# IA-prop-raspberry.net
KiCad netlist of a schematic drawn in EAGLE
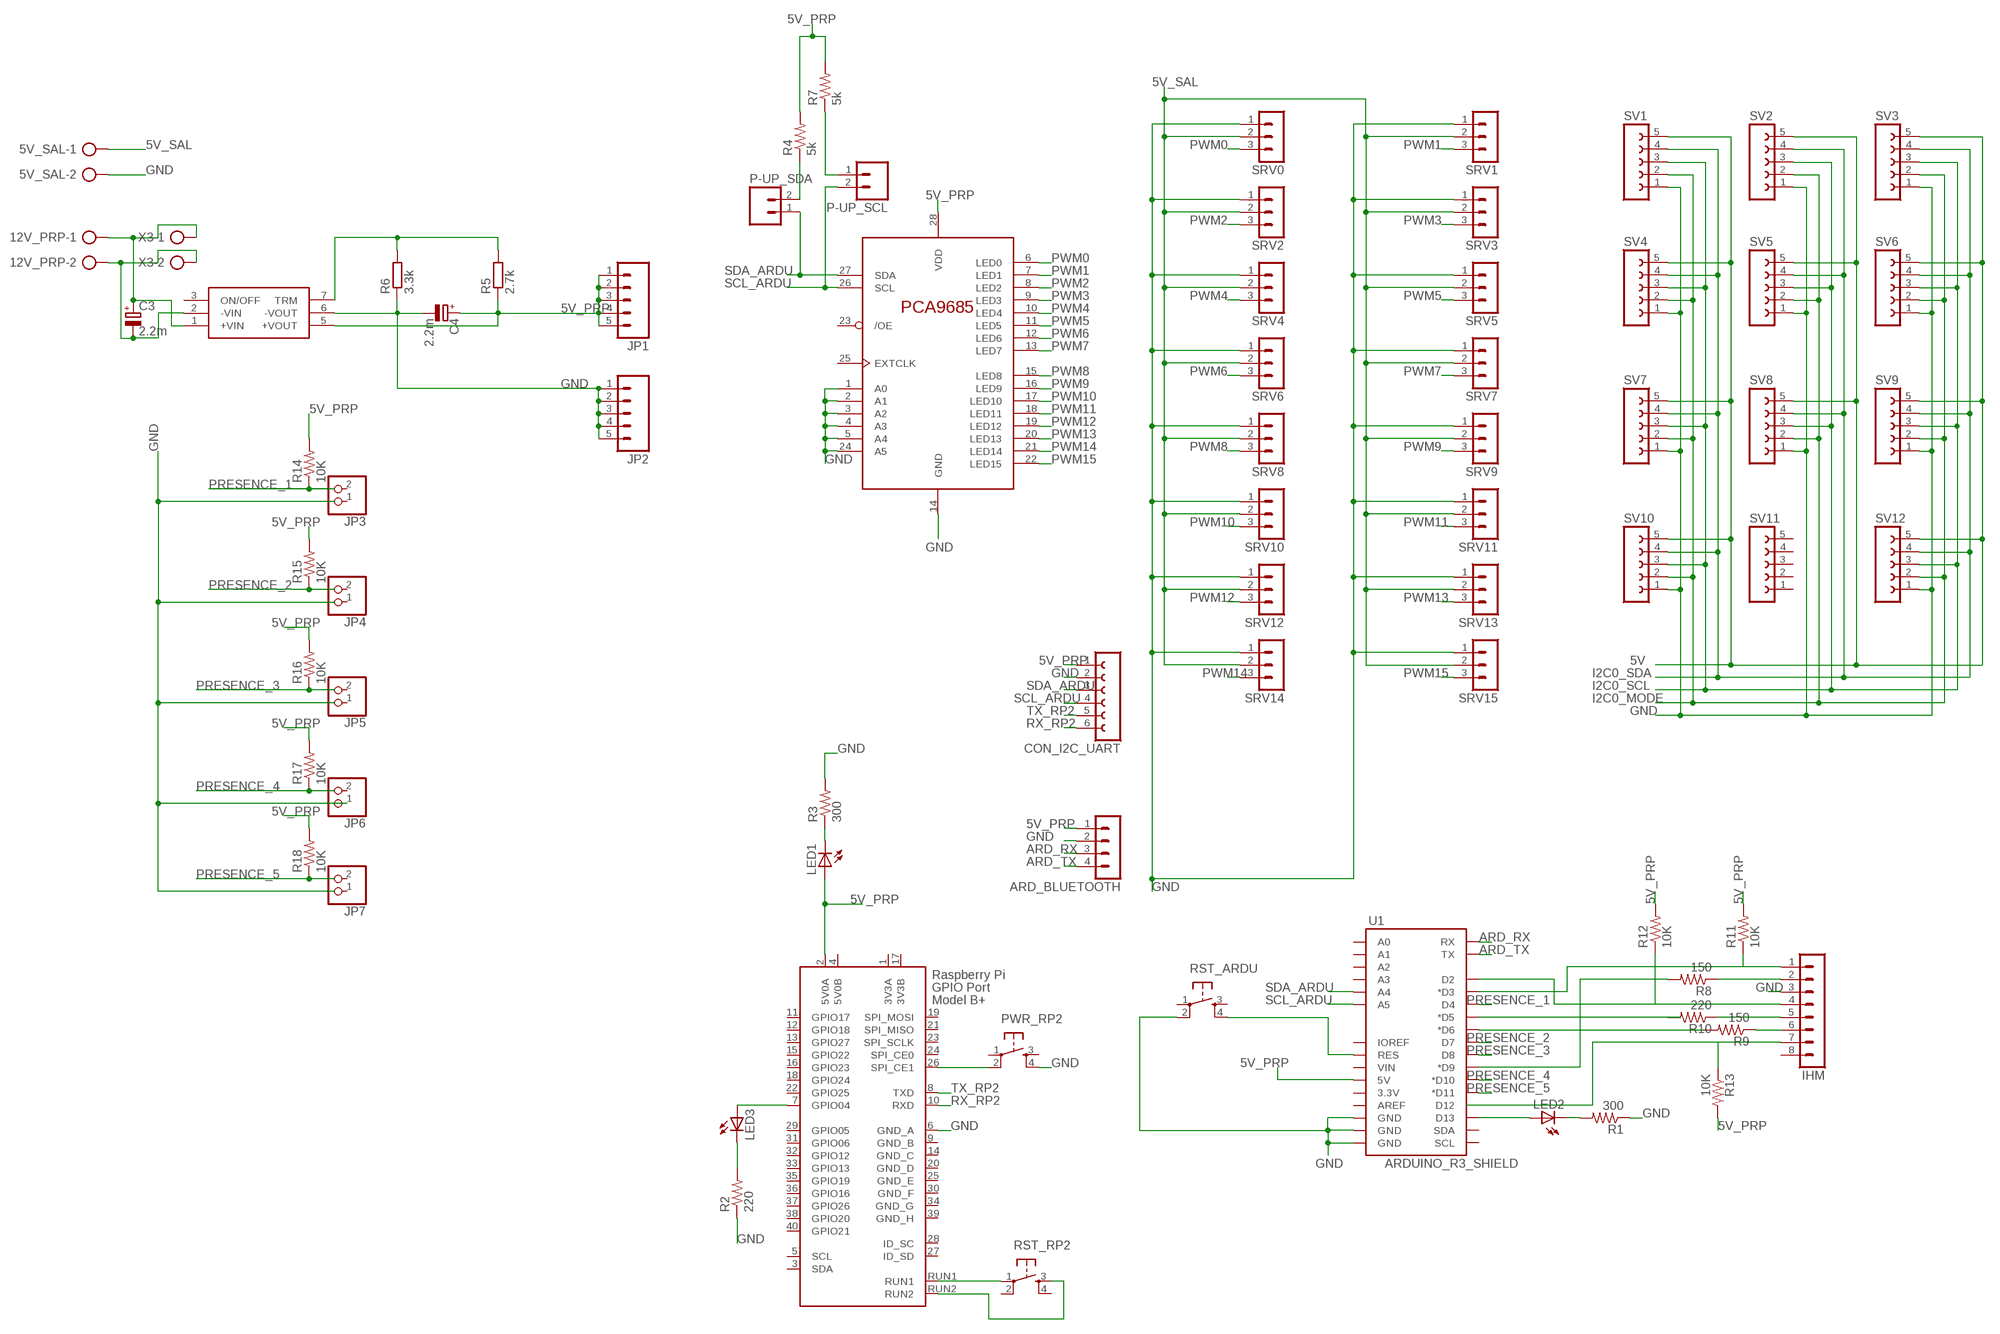
[diagram p0: schematic, sheet 1]

(export (version "E")
  (design (tool "Eeschema 10.0.6"))
  (components
    (comp (ref "5V_SAL")
      (value "AK300/2")
      (footprint "eagle-import:AK300_2")
      (fields (field (name "OC_FARNELL") "unknown") (field (name "OC_NEWARK") "unknown"))
      (libsource (lib "eagle-import") (part "AK300/2"))
    )
    (comp (ref "12V_PRP")
      (value "AK300/2")
      (footprint "eagle-import:AK300_2")
      (libsource (lib "eagle-import") (part "AK300/2"))
    )
    (comp (ref "ARD_BLUETOOTH")
      (value "MA04-1")
      (footprint "eagle-import:MA04-1")
      (libsource (lib "eagle-import") (part "MA04-1"))
    )
    (comp (ref "C3")
      (value "2.2m")
      (footprint "eagle-import:E5-13")
      (libsource (lib "eagle-import") (part "CPOL-EUE5-13"))
    )
    (comp (ref "C4")
      (value "2.2m")
      (footprint "eagle-import:E5-13")
      (libsource (lib "eagle-import") (part "CPOL-EUE5-13"))
    )
    (comp (ref "CON_I2C_UART")
      (value "FE06-1")
      (footprint "eagle-import:FE06")
      (fields (field (name "OC_FARNELL") "unknown") (field (name "OC_NEWARK") "unknown"))
      (libsource (lib "eagle-import") (part "FE06-1"))
    )
    (comp (ref "IHM")
      (value "MA08-1")
      (footprint "eagle-import:MA08-1")
      (libsource (lib "eagle-import") (part "MA08-1"))
    )
    (comp (ref "JP1")
      (value "M05PTH")
      (footprint "eagle-import:1X05")
      (libsource (lib "eagle-import") (part "M05PTH"))
    )
    (comp (ref "JP2")
      (value "M05PTH")
      (footprint "eagle-import:1X05")
      (libsource (lib "eagle-import") (part "M05PTH"))
    )
    (comp (ref "JP3")
      (value "PINHD-1X2")
      (footprint "eagle-import:1X02")
      (libsource (lib "eagle-import") (part "PINHD-1X2"))
    )
    (comp (ref "JP4")
      (value "PINHD-1X2")
      (footprint "eagle-import:1X02")
      (libsource (lib "eagle-import") (part "PINHD-1X2"))
    )
    (comp (ref "JP5")
      (value "PINHD-1X2")
      (footprint "eagle-import:1X02")
      (libsource (lib "eagle-import") (part "PINHD-1X2"))
    )
    (comp (ref "JP6")
      (value "PINHD-1X2")
      (footprint "eagle-import:1X02")
      (libsource (lib "eagle-import") (part "PINHD-1X2"))
    )
    (comp (ref "JP7")
      (value "PINHD-1X2")
      (footprint "eagle-import:1X02")
      (libsource (lib "eagle-import") (part "PINHD-1X2"))
    )
    (comp (ref "LED1")
      (value "LED3MM")
      (footprint "eagle-import:LED3MM")
      (libsource (lib "eagle-import") (part "LED3MM"))
    )
    (comp (ref "LED2")
      (value "LED3MM")
      (footprint "eagle-import:LED3MM")
      (libsource (lib "eagle-import") (part "LED3MM"))
    )
    (comp (ref "LED3")
      (value "LED3MM")
      (footprint "eagle-import:LED3MM")
      (libsource (lib "eagle-import") (part "LED3MM"))
    )
    (comp (ref "P-UP_SCL")
      (value "M02PTH")
      (footprint "eagle-import:1X02")
      (libsource (lib "eagle-import") (part "M02PTH"))
    )
    (comp (ref "P-UP_SDA")
      (value "M02PTH")
      (footprint "eagle-import:1X02")
      (libsource (lib "eagle-import") (part "M02PTH"))
    )
    (comp (ref "PWR_RP2")
      (value "TAC_SWITCHPTH")
      (footprint "eagle-import:TACTILE-PTH")
      (libsource (lib "eagle-import") (part "TAC_SWITCHPTH"))
    )
    (comp (ref "R1")
      (value "300")
      (footprint "eagle-import:AXIAL-0.3")
      (libsource (lib "eagle-import") (part "RESISTORAXIAL-0.3"))
    )
    (comp (ref "R2")
      (value "220")
      (footprint "eagle-import:AXIAL-0.3")
      (libsource (lib "eagle-import") (part "RESISTORAXIAL-0.3"))
    )
    (comp (ref "R3")
      (value "300")
      (footprint "eagle-import:AXIAL-0.3")
      (libsource (lib "eagle-import") (part "RESISTORAXIAL-0.3"))
    )
    (comp (ref "R4")
      (value "5k")
      (footprint "eagle-import:AXIAL-0.3")
      (libsource (lib "eagle-import") (part "RESISTORAXIAL-0.3"))
    )
    (comp (ref "R5")
      (value "2.7k")
      (footprint "eagle-import:0207_7")
      (libsource (lib "eagle-import") (part "R-EU_0207/7"))
    )
    (comp (ref "R6")
      (value "3.3k")
      (footprint "eagle-import:0207_7")
      (libsource (lib "eagle-import") (part "R-EU_0207/7"))
    )
    (comp (ref "R7")
      (value "5k")
      (footprint "eagle-import:AXIAL-0.3")
      (libsource (lib "eagle-import") (part "RESISTORAXIAL-0.3"))
    )
    (comp (ref "R8")
      (value "150")
      (footprint "eagle-import:AXIAL-0.3")
      (libsource (lib "eagle-import") (part "RESISTORAXIAL-0.3"))
    )
    (comp (ref "R9")
      (value "150")
      (footprint "eagle-import:AXIAL-0.3")
      (libsource (lib "eagle-import") (part "RESISTORAXIAL-0.3"))
    )
    (comp (ref "R10")
      (value "220")
      (footprint "eagle-import:AXIAL-0.3")
      (libsource (lib "eagle-import") (part "RESISTORAXIAL-0.3"))
    )
    (comp (ref "R11")
      (value "10K")
      (footprint "eagle-import:AXIAL-0.3")
      (libsource (lib "eagle-import") (part "RESISTORAXIAL-0.3"))
    )
    (comp (ref "R12")
      (value "10K")
      (footprint "eagle-import:AXIAL-0.3")
      (libsource (lib "eagle-import") (part "RESISTORAXIAL-0.3"))
    )
    (comp (ref "R13")
      (value "10K")
      (footprint "eagle-import:AXIAL-0.3")
      (libsource (lib "eagle-import") (part "RESISTORAXIAL-0.3"))
    )
    (comp (ref "R14")
      (value "10K")
      (footprint "eagle-import:AXIAL-0.3")
      (libsource (lib "eagle-import") (part "RESISTORAXIAL-0.3"))
    )
    (comp (ref "R15")
      (value "10K")
      (footprint "eagle-import:AXIAL-0.3")
      (libsource (lib "eagle-import") (part "RESISTORAXIAL-0.3"))
    )
    (comp (ref "R16")
      (value "10K")
      (footprint "eagle-import:AXIAL-0.3")
      (libsource (lib "eagle-import") (part "RESISTORAXIAL-0.3"))
    )
    (comp (ref "R17")
      (value "10K")
      (footprint "eagle-import:AXIAL-0.3")
      (libsource (lib "eagle-import") (part "RESISTORAXIAL-0.3"))
    )
    (comp (ref "R18")
      (value "10K")
      (footprint "eagle-import:AXIAL-0.3")
      (libsource (lib "eagle-import") (part "RESISTORAXIAL-0.3"))
    )
    (comp (ref "RP2")
      (value "RASPI_BOARD_B+#_FP")
      (footprint "eagle-import:RASPI_BOARD_B+_FULL_PAD")
      (libsource (lib "eagle-import") (part "RASPI_BOARD_B+#_FP"))
    )
    (comp (ref "RST_ARDU")
      (value "TAC_SWITCHPTH")
      (footprint "eagle-import:TACTILE-PTH")
      (libsource (lib "eagle-import") (part "TAC_SWITCHPTH"))
    )
    (comp (ref "RST_RP2")
      (value "TAC_SWITCHPTH")
      (footprint "eagle-import:TACTILE-PTH")
      (libsource (lib "eagle-import") (part "TAC_SWITCHPTH"))
    )
    (comp (ref "SRV0")
      (value "MA03-1")
      (footprint "eagle-import:MA03-1")
      (libsource (lib "eagle-import") (part "MA03-1"))
    )
    (comp (ref "SRV1")
      (value "MA03-1")
      (footprint "eagle-import:MA03-1")
      (libsource (lib "eagle-import") (part "MA03-1"))
    )
    (comp (ref "SRV2")
      (value "MA03-1")
      (footprint "eagle-import:MA03-1")
      (libsource (lib "eagle-import") (part "MA03-1"))
    )
    (comp (ref "SRV3")
      (value "MA03-1")
      (footprint "eagle-import:MA03-1")
      (libsource (lib "eagle-import") (part "MA03-1"))
    )
    (comp (ref "SRV4")
      (value "MA03-1")
      (footprint "eagle-import:MA03-1")
      (libsource (lib "eagle-import") (part "MA03-1"))
    )
    (comp (ref "SRV5")
      (value "MA03-1")
      (footprint "eagle-import:MA03-1")
      (libsource (lib "eagle-import") (part "MA03-1"))
    )
    (comp (ref "SRV6")
      (value "MA03-1")
      (footprint "eagle-import:MA03-1")
      (libsource (lib "eagle-import") (part "MA03-1"))
    )
    (comp (ref "SRV7")
      (value "MA03-1")
      (footprint "eagle-import:MA03-1")
      (libsource (lib "eagle-import") (part "MA03-1"))
    )
    (comp (ref "SRV8")
      (value "MA03-1")
      (footprint "eagle-import:MA03-1")
      (libsource (lib "eagle-import") (part "MA03-1"))
    )
    (comp (ref "SRV9")
      (value "MA03-1")
      (footprint "eagle-import:MA03-1")
      (libsource (lib "eagle-import") (part "MA03-1"))
    )
    (comp (ref "SRV10")
      (value "MA03-1")
      (footprint "eagle-import:MA03-1")
      (libsource (lib "eagle-import") (part "MA03-1"))
    )
    (comp (ref "SRV11")
      (value "MA03-1")
      (footprint "eagle-import:MA03-1")
      (libsource (lib "eagle-import") (part "MA03-1"))
    )
    (comp (ref "SRV12")
      (value "MA03-1")
      (footprint "eagle-import:MA03-1")
      (libsource (lib "eagle-import") (part "MA03-1"))
    )
    (comp (ref "SRV13")
      (value "MA03-1")
      (footprint "eagle-import:MA03-1")
      (libsource (lib "eagle-import") (part "MA03-1"))
    )
    (comp (ref "SRV14")
      (value "MA03-1")
      (footprint "eagle-import:MA03-1")
      (libsource (lib "eagle-import") (part "MA03-1"))
    )
    (comp (ref "SRV15")
      (value "MA03-1")
      (footprint "eagle-import:MA03-1")
      (libsource (lib "eagle-import") (part "MA03-1"))
    )
    (comp (ref "SV1")
      (value "FE05-1")
      (footprint "eagle-import:FE05-1")
      (libsource (lib "eagle-import") (part "FE05-1"))
    )
    (comp (ref "SV2")
      (value "FE05-1")
      (footprint "eagle-import:FE05-1")
      (fields (field (name "OC_FARNELL") "unknown") (field (name "OC_NEWARK") "unknown"))
      (libsource (lib "eagle-import") (part "FE05-1"))
    )
    (comp (ref "SV3")
      (value "FE05-1")
      (footprint "eagle-import:FE05-1")
      (fields (field (name "OC_FARNELL") "unknown") (field (name "OC_NEWARK") "unknown"))
      (libsource (lib "eagle-import") (part "FE05-1"))
    )
    (comp (ref "SV4")
      (value "FE05-1")
      (footprint "eagle-import:FE05-1")
      (libsource (lib "eagle-import") (part "FE05-1"))
    )
    (comp (ref "SV5")
      (value "FE05-1")
      (footprint "eagle-import:FE05-1")
      (fields (field (name "OC_FARNELL") "unknown") (field (name "OC_NEWARK") "unknown"))
      (libsource (lib "eagle-import") (part "FE05-1"))
    )
    (comp (ref "SV6")
      (value "FE05-1")
      (footprint "eagle-import:FE05-1")
      (fields (field (name "OC_FARNELL") "unknown") (field (name "OC_NEWARK") "unknown"))
      (libsource (lib "eagle-import") (part "FE05-1"))
    )
    (comp (ref "SV7")
      (value "FE05-1")
      (footprint "eagle-import:FE05-1")
      (libsource (lib "eagle-import") (part "FE05-1"))
    )
    (comp (ref "SV8")
      (value "FE05-1")
      (footprint "eagle-import:FE05-1")
      (fields (field (name "OC_FARNELL") "unknown") (field (name "OC_NEWARK") "unknown"))
      (libsource (lib "eagle-import") (part "FE05-1"))
    )
    (comp (ref "SV9")
      (value "FE05-1")
      (footprint "eagle-import:FE05-1")
      (fields (field (name "OC_FARNELL") "unknown") (field (name "OC_NEWARK") "unknown"))
      (libsource (lib "eagle-import") (part "FE05-1"))
    )
    (comp (ref "SV10")
      (value "FE05-1")
      (footprint "eagle-import:FE05-1")
      (libsource (lib "eagle-import") (part "FE05-1"))
    )
    (comp (ref "SV11")
      (value "FE05-1")
      (footprint "eagle-import:FE05-1")
      (fields (field (name "OC_FARNELL") "unknown") (field (name "OC_NEWARK") "unknown"))
      (libsource (lib "eagle-import") (part "FE05-1"))
    )
    (comp (ref "SV12")
      (value "FE05-1")
      (footprint "eagle-import:FE05-1")
      (fields (field (name "OC_FARNELL") "unknown") (field (name "OC_NEWARK") "unknown"))
      (libsource (lib "eagle-import") (part "FE05-1"))
    )
    (comp (ref "U$1")
      (value "PCA9685PW")
      (footprint "eagle-import:TSSOP28")
      (libsource (lib "eagle-import") (part "PCA9685PW"))
    )
    (comp (ref "U$2")
      (value "TEN25-1211TEN25-1211")
      (footprint "eagle-import:TEN25")
      (libsource (lib "eagle-import") (part "TEN25-1211TEN25-1211"))
    )
    (comp (ref "U1")
      (value "ARDUINO_R3_SHIELD")
      (footprint "eagle-import:UNO_R3_SHIELD")
      (libsource (lib "eagle-import") (part "ARDUINO_R3_SHIELD"))
    )
    (comp (ref "X3")
      (value "AK300/2")
      (footprint "eagle-import:AK300_2")
      (libsource (lib "eagle-import") (part "AK300/2"))
    )
  )
  (nets
    (net (code "1") (name "/3V3A") (class "Default")
      (node (ref "RP2") (pin "1") (pinfunction "3V3A_1") (pintype "power_in"))
    )
    (net (code "2") (name "/3V3B") (class "Default")
      (node (ref "RP2") (pin "17") (pinfunction "3V3B_17") (pintype "power_in"))
    )
    (net (code "3") (name "/5V") (class "Default")
      (node (ref "SV1") (pin "5") (pinfunction "5_5") (pintype "passive"))
      (node (ref "SV10") (pin "5") (pinfunction "5_5") (pintype "passive"))
      (node (ref "SV12") (pin "5") (pinfunction "5_5") (pintype "passive"))
      (node (ref "SV2") (pin "5") (pinfunction "5_5") (pintype "passive"))
      (node (ref "SV3") (pin "5") (pinfunction "5_5") (pintype "passive"))
      (node (ref "SV4") (pin "5") (pinfunction "5_5") (pintype "passive"))
      (node (ref "SV5") (pin "5") (pinfunction "5_5") (pintype "passive"))
      (node (ref "SV6") (pin "5") (pinfunction "5_5") (pintype "passive"))
      (node (ref "SV7") (pin "5") (pinfunction "5_5") (pintype "passive"))
      (node (ref "SV8") (pin "5") (pinfunction "5_5") (pintype "passive"))
      (node (ref "SV9") (pin "5") (pinfunction "5_5") (pintype "passive"))
    )
    (net (code "4") (name "/5V0B") (class "Default")
      (node (ref "RP2") (pin "4") (pinfunction "5V0B_4") (pintype "power_in"))
    )
    (net (code "5") (name "/5V_PRP") (class "Default")
      (node (ref "ARD_BLUETOOTH") (pin "1") (pinfunction "1_1") (pintype "passive"))
      (node (ref "C4") (pin "+") (pinfunction "+_+") (pintype "passive"))
      (node (ref "CON_I2C_UART") (pin "1") (pinfunction "1_1") (pintype "passive"))
      (node (ref "JP1") (pin "1") (pinfunction "1_1") (pintype "passive"))
      (node (ref "JP1") (pin "2") (pinfunction "2_2") (pintype "passive"))
      (node (ref "JP1") (pin "3") (pinfunction "3_3") (pintype "passive"))
      (node (ref "JP1") (pin "4") (pinfunction "4_4") (pintype "passive"))
      (node (ref "JP1") (pin "5") (pinfunction "5_5") (pintype "passive"))
      (node (ref "LED1") (pin "A") (pinfunction "A_A") (pintype "passive"))
      (node (ref "R11") (pin "P$2") (pinfunction "2_P$2") (pintype "passive"))
      (node (ref "R12") (pin "P$2") (pinfunction "2_P$2") (pintype "passive"))
      (node (ref "R13") (pin "P$2") (pinfunction "2_P$2") (pintype "passive"))
      (node (ref "R14") (pin "P$2") (pinfunction "2_P$2") (pintype "passive"))
      (node (ref "R15") (pin "P$2") (pinfunction "2_P$2") (pintype "passive"))
      (node (ref "R16") (pin "P$2") (pinfunction "2_P$2") (pintype "passive"))
      (node (ref "R17") (pin "P$2") (pinfunction "2_P$2") (pintype "passive"))
      (node (ref "R18") (pin "P$2") (pinfunction "2_P$2") (pintype "passive"))
      (node (ref "R4") (pin "P$2") (pinfunction "2_P$2") (pintype "passive"))
      (node (ref "R5") (pin "1") (pinfunction "1_1") (pintype "passive"))
      (node (ref "R7") (pin "P$2") (pinfunction "2_P$2") (pintype "passive"))
      (node (ref "RP2") (pin "2") (pinfunction "5V0A_2") (pintype "power_in"))
      (node (ref "U$1") (pin "28") (pinfunction "VDD_28") (pintype "power_in"))
      (node (ref "U$2") (pin "5") (pinfunction "+VOUT_5") (pintype "bidirectional"))
      (node (ref "U1") (pin "5V") (pinfunction "5V_5V") (pintype "bidirectional"))
    )
    (net (code "6") (name "/5V_SAL") (class "Default")
      (node (ref "5V_SAL") (pin "1") (pinfunction "KL_1") (pintype "passive"))
      (node (ref "SRV0") (pin "2") (pinfunction "2_2") (pintype "passive"))
      (node (ref "SRV1") (pin "2") (pinfunction "2_2") (pintype "passive"))
      (node (ref "SRV10") (pin "2") (pinfunction "2_2") (pintype "passive"))
      (node (ref "SRV11") (pin "2") (pinfunction "2_2") (pintype "passive"))
      (node (ref "SRV12") (pin "2") (pinfunction "2_2") (pintype "passive"))
      (node (ref "SRV13") (pin "2") (pinfunction "2_2") (pintype "passive"))
      (node (ref "SRV14") (pin "2") (pinfunction "2_2") (pintype "passive"))
      (node (ref "SRV15") (pin "2") (pinfunction "2_2") (pintype "passive"))
      (node (ref "SRV2") (pin "2") (pinfunction "2_2") (pintype "passive"))
      (node (ref "SRV3") (pin "2") (pinfunction "2_2") (pintype "passive"))
      (node (ref "SRV4") (pin "2") (pinfunction "2_2") (pintype "passive"))
      (node (ref "SRV5") (pin "2") (pinfunction "2_2") (pintype "passive"))
      (node (ref "SRV6") (pin "2") (pinfunction "2_2") (pintype "passive"))
      (node (ref "SRV7") (pin "2") (pinfunction "2_2") (pintype "passive"))
      (node (ref "SRV8") (pin "2") (pinfunction "2_2") (pintype "passive"))
      (node (ref "SRV9") (pin "2") (pinfunction "2_2") (pintype "passive"))
    )
    (net (code "7") (name "/ARD_RX") (class "Default")
      (node (ref "ARD_BLUETOOTH") (pin "3") (pinfunction "3_3") (pintype "passive"))
      (node (ref "U1") (pin "RX") (pinfunction "RX_RX") (pintype "bidirectional"))
    )
    (net (code "8") (name "/ARD_TX") (class "Default")
      (node (ref "ARD_BLUETOOTH") (pin "4") (pinfunction "4_4") (pintype "passive"))
      (node (ref "U1") (pin "TX") (pinfunction "TX_TX") (pintype "bidirectional"))
    )
    (net (code "9") (name "/GND") (class "Default")
      (node (ref "5V_SAL") (pin "2") (pinfunction "KL_2") (pintype "passive"))
      (node (ref "ARD_BLUETOOTH") (pin "2") (pinfunction "2_2") (pintype "passive"))
      (node (ref "C4") (pin "-") (pinfunction "-_-") (pintype "passive"))
      (node (ref "CON_I2C_UART") (pin "2") (pinfunction "2_2") (pintype "passive"))
      (node (ref "IHM") (pin "3") (pinfunction "3_3") (pintype "passive"))
      (node (ref "JP2") (pin "1") (pinfunction "1_1") (pintype "passive"))
      (node (ref "JP2") (pin "2") (pinfunction "2_2") (pintype "passive"))
      (node (ref "JP2") (pin "3") (pinfunction "3_3") (pintype "passive"))
      (node (ref "JP2") (pin "4") (pinfunction "4_4") (pintype "passive"))
      (node (ref "JP2") (pin "5") (pinfunction "5_5") (pintype "passive"))
      (node (ref "JP6") (pin "1") (pinfunction "1_1") (pintype "passive"))
      (node (ref "PWR_RP2") (pin "4") (pinfunction "4_4") (pintype "passive"))
      (node (ref "R1") (pin "P$1") (pinfunction "1_P$1") (pintype "passive"))
      (node (ref "R2") (pin "P$1") (pinfunction "1_P$1") (pintype "passive"))
      (node (ref "R3") (pin "P$2") (pinfunction "2_P$2") (pintype "passive"))
      (node (ref "R6") (pin "1") (pinfunction "1_1") (pintype "passive"))
      (node (ref "RP2") (pin "6") (pinfunction "GND_A_6") (pintype "power_in"))
      (node (ref "RST_ARDU") (pin "2") (pinfunction "2_2") (pintype "passive"))
      (node (ref "SRV0") (pin "1") (pinfunction "1_1") (pintype "passive"))
      (node (ref "SRV1") (pin "1") (pinfunction "1_1") (pintype "passive"))
      (node (ref "SRV10") (pin "1") (pinfunction "1_1") (pintype "passive"))
      (node (ref "SRV11") (pin "1") (pinfunction "1_1") (pintype "passive"))
      (node (ref "SRV12") (pin "1") (pinfunction "1_1") (pintype "passive"))
      (node (ref "SRV13") (pin "1") (pinfunction "1_1") (pintype "passive"))
      (node (ref "SRV14") (pin "1") (pinfunction "1_1") (pintype "passive"))
      (node (ref "SRV15") (pin "1") (pinfunction "1_1") (pintype "passive"))
      (node (ref "SRV2") (pin "1") (pinfunction "1_1") (pintype "passive"))
      (node (ref "SRV3") (pin "1") (pinfunction "1_1") (pintype "passive"))
      (node (ref "SRV4") (pin "1") (pinfunction "1_1") (pintype "passive"))
      (node (ref "SRV5") (pin "1") (pinfunction "1_1") (pintype "passive"))
      (node (ref "SRV6") (pin "1") (pinfunction "1_1") (pintype "passive"))
      (node (ref "SRV7") (pin "1") (pinfunction "1_1") (pintype "passive"))
      (node (ref "SRV8") (pin "1") (pinfunction "1_1") (pintype "passive"))
      (node (ref "SRV9") (pin "1") (pinfunction "1_1") (pintype "passive"))
      (node (ref "SV1") (pin "1") (pinfunction "1_1") (pintype "passive"))
      (node (ref "SV10") (pin "1") (pinfunction "1_1") (pintype "passive"))
      (node (ref "SV12") (pin "1") (pinfunction "1_1") (pintype "passive"))
      (node (ref "SV2") (pin "1") (pinfunction "1_1") (pintype "passive"))
      (node (ref "SV3") (pin "1") (pinfunction "1_1") (pintype "passive"))
      (node (ref "SV4") (pin "1") (pinfunction "1_1") (pintype "passive"))
      (node (ref "SV5") (pin "1") (pinfunction "1_1") (pintype "passive"))
      (node (ref "SV6") (pin "1") (pinfunction "1_1") (pintype "passive"))
      (node (ref "SV7") (pin "1") (pinfunction "1_1") (pintype "passive"))
      (node (ref "SV8") (pin "1") (pinfunction "1_1") (pintype "passive"))
      (node (ref "SV9") (pin "1") (pinfunction "1_1") (pintype "passive"))
      (node (ref "U$1") (pin "1") (pinfunction "A0_1") (pintype "bidirectional"))
      (node (ref "U$1") (pin "14") (pinfunction "GND_14") (pintype "power_in"))
      (node (ref "U$1") (pin "2") (pinfunction "A1_2") (pintype "bidirectional"))
      (node (ref "U$1") (pin "24") (pinfunction "A5_24") (pintype "bidirectional"))
      (node (ref "U$1") (pin "3") (pinfunction "A2_3") (pintype "bidirectional"))
      (node (ref "U$1") (pin "4") (pinfunction "A3_4") (pintype "bidirectional"))
      (node (ref "U$1") (pin "5") (pinfunction "A4_5") (pintype "bidirectional"))
      (node (ref "U$2") (pin "6") (pinfunction "-VOUT_6") (pintype "bidirectional"))
      (node (ref "U1") (pin "GND@0") (pinfunction "GND_GND@0") (pintype "bidirectional"))
      (node (ref "U1") (pin "GND@1") (pinfunction "GND_GND@1") (pintype "bidirectional"))
      (node (ref "U1") (pin "GND@2") (pinfunction "GND_GND@2") (pintype "bidirectional"))
    )
    (net (code "10") (name "/GND_B") (class "Default")
      (node (ref "RP2") (pin "9") (pinfunction "GND_B_9") (pintype "power_in"))
    )
    (net (code "11") (name "/GND_C") (class "Default")
      (node (ref "RP2") (pin "14") (pinfunction "GND_C_14") (pintype "power_in"))
    )
    (net (code "12") (name "/GND_D") (class "Default")
      (node (ref "RP2") (pin "20") (pinfunction "GND_D_20") (pintype "power_in"))
    )
    (net (code "13") (name "/GND_E") (class "Default")
      (node (ref "RP2") (pin "25") (pinfunction "GND_E_25") (pintype "power_in"))
    )
    (net (code "14") (name "/GND_F") (class "Default")
      (node (ref "RP2") (pin "30") (pinfunction "GND_F_30") (pintype "power_in"))
    )
    (net (code "15") (name "/GND_G") (class "Default")
      (node (ref "RP2") (pin "34") (pinfunction "GND_G_34") (pintype "power_in"))
    )
    (net (code "16") (name "/GND_H") (class "Default")
      (node (ref "RP2") (pin "39") (pinfunction "GND_H_39") (pintype "power_in"))
    )
    (net (code "17") (name "/I2C0_MODE") (class "Default")
      (node (ref "SV1") (pin "2") (pinfunction "2_2") (pintype "passive"))
      (node (ref "SV10") (pin "2") (pinfunction "2_2") (pintype "passive"))
      (node (ref "SV12") (pin "2") (pinfunction "2_2") (pintype "passive"))
      (node (ref "SV2") (pin "2") (pinfunction "2_2") (pintype "passive"))
      (node (ref "SV3") (pin "2") (pinfunction "2_2") (pintype "passive"))
      (node (ref "SV4") (pin "2") (pinfunction "2_2") (pintype "passive"))
      (node (ref "SV5") (pin "2") (pinfunction "2_2") (pintype "passive"))
      (node (ref "SV6") (pin "2") (pinfunction "2_2") (pintype "passive"))
      (node (ref "SV7") (pin "2") (pinfunction "2_2") (pintype "passive"))
      (node (ref "SV8") (pin "2") (pinfunction "2_2") (pintype "passive"))
      (node (ref "SV9") (pin "2") (pinfunction "2_2") (pintype "passive"))
    )
    (net (code "18") (name "/I2C0_SCL") (class "Default")
      (node (ref "SV1") (pin "3") (pinfunction "3_3") (pintype "passive"))
      (node (ref "SV10") (pin "3") (pinfunction "3_3") (pintype "passive"))
      (node (ref "SV12") (pin "3") (pinfunction "3_3") (pintype "passive"))
      (node (ref "SV2") (pin "3") (pinfunction "3_3") (pintype "passive"))
      (node (ref "SV3") (pin "3") (pinfunction "3_3") (pintype "passive"))
      (node (ref "SV4") (pin "3") (pinfunction "3_3") (pintype "passive"))
      (node (ref "SV5") (pin "3") (pinfunction "3_3") (pintype "passive"))
      (node (ref "SV6") (pin "3") (pinfunction "3_3") (pintype "passive"))
      (node (ref "SV7") (pin "3") (pinfunction "3_3") (pintype "passive"))
      (node (ref "SV8") (pin "3") (pinfunction "3_3") (pintype "passive"))
      (node (ref "SV9") (pin "3") (pinfunction "3_3") (pintype "passive"))
    )
    (net (code "19") (name "/I2C0_SDA") (class "Default")
      (node (ref "SV1") (pin "4") (pinfunction "4_4") (pintype "passive"))
      (node (ref "SV10") (pin "4") (pinfunction "4_4") (pintype "passive"))
      (node (ref "SV12") (pin "4") (pinfunction "4_4") (pintype "passive"))
      (node (ref "SV2") (pin "4") (pinfunction "4_4") (pintype "passive"))
      (node (ref "SV3") (pin "4") (pinfunction "4_4") (pintype "passive"))
      (node (ref "SV4") (pin "4") (pinfunction "4_4") (pintype "passive"))
      (node (ref "SV5") (pin "4") (pinfunction "4_4") (pintype "passive"))
      (node (ref "SV6") (pin "4") (pinfunction "4_4") (pintype "passive"))
      (node (ref "SV7") (pin "4") (pinfunction "4_4") (pintype "passive"))
      (node (ref "SV8") (pin "4") (pinfunction "4_4") (pintype "passive"))
      (node (ref "SV9") (pin "4") (pinfunction "4_4") (pintype "passive"))
    )
    (net (code "20") (name "/PRESENCE_1") (class "Default")
      (node (ref "R14") (pin "P$1") (pinfunction "1_P$1") (pintype "passive"))
      (node (ref "U1") (pin "D4") (pinfunction "D4_D4") (pintype "bidirectional"))
    )
    (net (code "21") (name "/PRESENCE_2") (class "Default")
      (node (ref "R15") (pin "P$1") (pinfunction "1_P$1") (pintype "passive"))
      (node (ref "U1") (pin "D7") (pinfunction "D7_D7") (pintype "bidirectional"))
    )
    (net (code "22") (name "/PRESENCE_3") (class "Default")
      (node (ref "R16") (pin "P$1") (pinfunction "1_P$1") (pintype "passive"))
      (node (ref "U1") (pin "D8") (pinfunction "D8_D8") (pintype "bidirectional"))
    )
    (net (code "23") (name "/PRESENCE_4") (class "Default")
      (node (ref "R17") (pin "P$1") (pinfunction "1_P$1") (pintype "passive"))
      (node (ref "U1") (pin "D10") (pinfunction "*D10_D10") (pintype "bidirectional"))
    )
    (net (code "24") (name "/PRESENCE_5") (class "Default")
      (node (ref "R18") (pin "P$1") (pinfunction "1_P$1") (pintype "passive"))
      (node (ref "U1") (pin "D11") (pinfunction "*D11_D11") (pintype "bidirectional"))
    )
    (net (code "25") (name "/PWM0") (class "Default")
      (node (ref "SRV0") (pin "3") (pinfunction "3_3") (pintype "passive"))
      (node (ref "U$1") (pin "6") (pinfunction "LED0_6") (pintype "bidirectional"))
    )
    (net (code "26") (name "/PWM1") (class "Default")
      (node (ref "SRV1") (pin "3") (pinfunction "3_3") (pintype "passive"))
      (node (ref "U$1") (pin "7") (pinfunction "LED1_7") (pintype "bidirectional"))
    )
    (net (code "27") (name "/PWM2") (class "Default")
      (node (ref "SRV2") (pin "3") (pinfunction "3_3") (pintype "passive"))
      (node (ref "U$1") (pin "8") (pinfunction "LED2_8") (pintype "bidirectional"))
    )
    (net (code "28") (name "/PWM3") (class "Default")
      (node (ref "SRV3") (pin "3") (pinfunction "3_3") (pintype "passive"))
      (node (ref "U$1") (pin "9") (pinfunction "LED3_9") (pintype "bidirectional"))
    )
    (net (code "29") (name "/PWM4") (class "Default")
      (node (ref "SRV4") (pin "3") (pinfunction "3_3") (pintype "passive"))
      (node (ref "U$1") (pin "10") (pinfunction "LED4_10") (pintype "bidirectional"))
    )
    (net (code "30") (name "/PWM5") (class "Default")
      (node (ref "SRV5") (pin "3") (pinfunction "3_3") (pintype "passive"))
      (node (ref "U$1") (pin "11") (pinfunction "LED5_11") (pintype "bidirectional"))
    )
    (net (code "31") (name "/PWM6") (class "Default")
      (node (ref "SRV6") (pin "3") (pinfunction "3_3") (pintype "passive"))
      (node (ref "U$1") (pin "12") (pinfunction "LED6_12") (pintype "bidirectional"))
    )
    (net (code "32") (name "/PWM7") (class "Default")
      (node (ref "SRV7") (pin "3") (pinfunction "3_3") (pintype "passive"))
      (node (ref "U$1") (pin "13") (pinfunction "LED7_13") (pintype "bidirectional"))
    )
    (net (code "33") (name "/PWM8") (class "Default")
      (node (ref "SRV8") (pin "3") (pinfunction "3_3") (pintype "passive"))
      (node (ref "U$1") (pin "15") (pinfunction "LED8_15") (pintype "bidirectional"))
    )
    (net (code "34") (name "/PWM9") (class "Default")
      (node (ref "SRV9") (pin "3") (pinfunction "3_3") (pintype "passive"))
      (node (ref "U$1") (pin "16") (pinfunction "LED9_16") (pintype "bidirectional"))
    )
    (net (code "35") (name "/PWM10") (class "Default")
      (node (ref "SRV10") (pin "3") (pinfunction "3_3") (pintype "passive"))
      (node (ref "U$1") (pin "17") (pinfunction "LED10_17") (pintype "bidirectional"))
    )
    (net (code "36") (name "/PWM11") (class "Default")
      (node (ref "SRV11") (pin "3") (pinfunction "3_3") (pintype "passive"))
      (node (ref "U$1") (pin "18") (pinfunction "LED11_18") (pintype "bidirectional"))
    )
    (net (code "37") (name "/PWM12") (class "Default")
      (node (ref "SRV12") (pin "3") (pinfunction "3_3") (pintype "passive"))
      (node (ref "U$1") (pin "19") (pinfunction "LED12_19") (pintype "bidirectional"))
    )
    (net (code "38") (name "/PWM13") (class "Default")
      (node (ref "SRV13") (pin "3") (pinfunction "3_3") (pintype "passive"))
      (node (ref "U$1") (pin "20") (pinfunction "LED13_20") (pintype "bidirectional"))
    )
    (net (code "39") (name "/PWM14") (class "Default")
      (node (ref "SRV14") (pin "3") (pinfunction "3_3") (pintype "passive"))
      (node (ref "U$1") (pin "21") (pinfunction "LED14_21") (pintype "bidirectional"))
    )
    (net (code "40") (name "/PWM15") (class "Default")
      (node (ref "SRV15") (pin "3") (pinfunction "3_3") (pintype "passive"))
      (node (ref "U$1") (pin "22") (pinfunction "LED15_22") (pintype "bidirectional"))
    )
    (net (code "41") (name "/RX_RP2") (class "Default")
      (node (ref "CON_I2C_UART") (pin "6") (pinfunction "6_6") (pintype "passive"))
      (node (ref "RP2") (pin "10") (pinfunction "RXD_10") (pintype "bidirectional"))
    )
    (net (code "42") (name "/SCL_ARDU") (class "Default")
      (node (ref "CON_I2C_UART") (pin "4") (pinfunction "4_4") (pintype "passive"))
      (node (ref "P-UP_SCL") (pin "2") (pinfunction "2_2") (pintype "passive"))
      (node (ref "U$1") (pin "26") (pinfunction "SCL_26") (pintype "bidirectional"))
      (node (ref "U1") (pin "A5") (pinfunction "A5_A5") (pintype "bidirectional"))
    )
    (net (code "43") (name "/SDA_ARDU") (class "Default")
      (node (ref "CON_I2C_UART") (pin "3") (pinfunction "3_3") (pintype "passive"))
      (node (ref "P-UP_SDA") (pin "1") (pinfunction "1_1") (pintype "passive"))
      (node (ref "U$1") (pin "27") (pinfunction "SDA_27") (pintype "bidirectional"))
      (node (ref "U1") (pin "A4") (pinfunction "A4_A4") (pintype "bidirectional"))
    )
    (net (code "44") (name "/TX_RP2") (class "Default")
      (node (ref "CON_I2C_UART") (pin "5") (pinfunction "5_5") (pintype "passive"))
      (node (ref "RP2") (pin "8") (pinfunction "TXD_8") (pintype "bidirectional"))
    )
    (net (code "45") (name "Net-(12V_PRPA-KL)") (class "Default")
      (node (ref "12V_PRP") (pin "1") (pinfunction "KL_1") (pintype "passive"))
      (node (ref "C3") (pin "+") (pinfunction "+_+") (pintype "passive"))
      (node (ref "U$2") (pin "1") (pinfunction "+VIN_1") (pintype "bidirectional"))
      (node (ref "X3") (pin "1") (pinfunction "KL_1") (pintype "passive"))
    )
    (net (code "46") (name "Net-(12V_PRPB-KL)") (class "Default")
      (node (ref "12V_PRP") (pin "2") (pinfunction "KL_2") (pintype "passive"))
      (node (ref "C3") (pin "-") (pinfunction "-_-") (pintype "passive"))
      (node (ref "U$2") (pin "2") (pinfunction "-VIN_2") (pintype "bidirectional"))
      (node (ref "X3") (pin "2") (pinfunction "KL_2") (pintype "passive"))
    )
    (net (code "47") (name "Net-(LED1-C)") (class "Default")
      (node (ref "LED1") (pin "K") (pinfunction "C_K") (pintype "passive"))
      (node (ref "R3") (pin "P$1") (pinfunction "1_P$1") (pintype "passive"))
    )
    (net (code "48") (name "Net-(LED2-C)") (class "Default")
      (node (ref "LED2") (pin "K") (pinfunction "C_K") (pintype "passive"))
      (node (ref "R1") (pin "P$2") (pinfunction "2_P$2") (pintype "passive"))
    )
    (net (code "49") (name "Net-(LED2-PadA)") (class "Default")
      (node (ref "LED2") (pin "A") (pinfunction "A_A") (pintype "passive"))
      (node (ref "U1") (pin "D13") (pinfunction "D13_D13") (pintype "bidirectional"))
    )
    (net (code "50") (name "Net-(LED3-C)") (class "Default")
      (node (ref "LED3") (pin "K") (pinfunction "C_K") (pintype "passive"))
      (node (ref "R2") (pin "P$2") (pinfunction "2_P$2") (pintype "passive"))
    )
    (net (code "51") (name "Net-(R4-1)") (class "Default")
      (node (ref "P-UP_SDA") (pin "2") (pinfunction "2_2") (pintype "passive"))
      (node (ref "R4") (pin "P$1") (pinfunction "1_P$1") (pintype "passive"))
    )
    (net (code "52") (name "Net-(R7-1)") (class "Default")
      (node (ref "P-UP_SCL") (pin "1") (pinfunction "1_1") (pintype "passive"))
      (node (ref "R7") (pin "P$1") (pinfunction "1_P$1") (pintype "passive"))
    )
    (net (code "53") (name "Net-(R8-1)") (class "Default")
      (node (ref "IHM") (pin "2") (pinfunction "2_2") (pintype "passive"))
      (node (ref "R8") (pin "P$1") (pinfunction "1_P$1") (pintype "passive"))
    )
    (net (code "54") (name "Net-(R8-2)") (class "Default")
      (node (ref "R8") (pin "P$2") (pinfunction "2_P$2") (pintype "passive"))
      (node (ref "U1") (pin "D9") (pinfunction "*D9_D9") (pintype "bidirectional"))
    )
    (net (code "55") (name "Net-(R9-1)") (class "Default")
      (node (ref "IHM") (pin "6") (pinfunction "6_6") (pintype "passive"))
      (node (ref "R9") (pin "P$1") (pinfunction "1_P$1") (pintype "passive"))
    )
    (net (code "56") (name "Net-(R9-2)") (class "Default")
      (node (ref "R9") (pin "P$2") (pinfunction "2_P$2") (pintype "passive"))
      (node (ref "U1") (pin "D6") (pinfunction "*D6_D6") (pintype "bidirectional"))
    )
    (net (code "57") (name "Net-(R10-1)") (class "Default")
      (node (ref "IHM") (pin "5") (pinfunction "5_5") (pintype "passive"))
      (node (ref "R10") (pin "P$1") (pinfunction "1_P$1") (pintype "passive"))
    )
    (net (code "58") (name "Net-(R11-1)") (class "Default")
      (node (ref "IHM") (pin "1") (pinfunction "1_1") (pintype "passive"))
      (node (ref "R11") (pin "P$1") (pinfunction "1_P$1") (pintype "passive"))
      (node (ref "U1") (pin "D3") (pinfunction "*D3_D3") (pintype "bidirectional"))
    )
    (net (code "59") (name "Net-(R12-1)") (class "Default")
      (node (ref "IHM") (pin "4") (pinfunction "4_4") (pintype "passive"))
      (node (ref "R12") (pin "P$1") (pinfunction "1_P$1") (pintype "passive"))
      (node (ref "U1") (pin "D2") (pinfunction "D2_D2") (pintype "bidirectional"))
    )
    (net (code "60") (name "Net-(R13-1)") (class "Default")
      (node (ref "IHM") (pin "7") (pinfunction "7_7") (pintype "passive"))
      (node (ref "R13") (pin "P$1") (pinfunction "1_P$1") (pintype "passive"))
    )
    (net (code "61") (name "Net-(RP2-GPIO04)") (class "Default")
      (node (ref "LED3") (pin "A") (pinfunction "A_A") (pintype "passive"))
      (node (ref "RP2") (pin "7") (pinfunction "GPIO04_7") (pintype "bidirectional"))
    )
    (net (code "62") (name "Net-(RP2-PadRUN1)") (class "Default")
      (node (ref "RP2") (pin "RUN1") (pinfunction "RUN1_RUN1") (pintype "bidirectional"))
      (node (ref "RST_RP2") (pin "1") (pinfunction "1_1") (pintype "passive"))
    )
    (net (code "63") (name "Net-(RP2-PadRUN2)") (class "Default")
      (node (ref "RP2") (pin "RUN2") (pinfunction "RUN2_RUN2") (pintype "bidirectional"))
      (node (ref "RST_RP2") (pin "3") (pinfunction "3_3") (pintype "passive"))
    )
    (net (code "64") (name "Net-(RP2-SPI_CE1)") (class "Default")
      (node (ref "PWR_RP2") (pin "2") (pinfunction "2_2") (pintype "passive"))
      (node (ref "RP2") (pin "26") (pinfunction "SPI_CE1_26") (pintype "bidirectional"))
    )
    (net (code "65") (name "Net-(RST_ARDU-Pad4)") (class "Default")
      (node (ref "RST_ARDU") (pin "4") (pinfunction "4_4") (pintype "passive"))
      (node (ref "U1") (pin "RES") (pinfunction "RES_RES") (pintype "bidirectional"))
    )
    (net (code "66") (name "Net-(U$2-TRM)") (class "Default")
      (node (ref "R5") (pin "2") (pinfunction "2_2") (pintype "passive"))
      (node (ref "R6") (pin "2") (pinfunction "2_2") (pintype "passive"))
      (node (ref "U$2") (pin "7") (pinfunction "TRM_7") (pintype "bidirectional"))
    )
    (net (code "67") (name "unconnected-(IHM-Pad8)") (class "Default")
      (node (ref "IHM") (pin "8") (pinfunction "8_8") (pintype "passive"))
    )
    (net (code "68") (name "unconnected-(JP3-Pad1)") (class "Default")
      (node (ref "JP3") (pin "1") (pinfunction "1_1") (pintype "passive"))
    )
    (net (code "69") (name "unconnected-(JP3-Pad2)") (class "Default")
      (node (ref "JP3") (pin "2") (pinfunction "2_2") (pintype "passive"))
    )
    (net (code "70") (name "unconnected-(JP4-Pad1)") (class "Default")
      (node (ref "JP4") (pin "1") (pinfunction "1_1") (pintype "passive"))
    )
    (net (code "71") (name "unconnected-(JP4-Pad2)") (class "Default")
      (node (ref "JP4") (pin "2") (pinfunction "2_2") (pintype "passive"))
    )
    (net (code "72") (name "unconnected-(JP5-Pad1)") (class "Default")
      (node (ref "JP5") (pin "1") (pinfunction "1_1") (pintype "passive"))
    )
    (net (code "73") (name "unconnected-(JP5-Pad2)") (class "Default")
      (node (ref "JP5") (pin "2") (pinfunction "2_2") (pintype "passive"))
    )
    (net (code "74") (name "unconnected-(JP6-Pad2)") (class "Default")
      (node (ref "JP6") (pin "2") (pinfunction "2_2") (pintype "passive"))
    )
    (net (code "75") (name "unconnected-(JP7-Pad1)") (class "Default")
      (node (ref "JP7") (pin "1") (pinfunction "1_1") (pintype "passive"))
    )
    (net (code "76") (name "unconnected-(JP7-Pad2)") (class "Default")
      (node (ref "JP7") (pin "2") (pinfunction "2_2") (pintype "passive"))
    )
    (net (code "77") (name "unconnected-(PWR_RP2-Pad1)") (class "Default")
      (node (ref "PWR_RP2") (pin "1") (pinfunction "1_1") (pintype "passive"))
    )
    (net (code "78") (name "unconnected-(PWR_RP2-Pad3)") (class "Default")
      (node (ref "PWR_RP2") (pin "3") (pinfunction "3_3") (pintype "passive"))
    )
    (net (code "79") (name "unconnected-(R10-2-PadP$2)") (class "Default")
      (node (ref "R10") (pin "P$2") (pinfunction "2_P$2") (pintype "passive"))
    )
    (net (code "80") (name "unconnected-(RP2-GPIO05-Pad29)") (class "Default")
      (node (ref "RP2") (pin "29") (pinfunction "GPIO05_29") (pintype "no_connect"))
    )
    (net (code "81") (name "unconnected-(RP2-GPIO06-Pad31)") (class "Default")
      (node (ref "RP2") (pin "31") (pinfunction "GPIO06_31") (pintype "no_connect"))
    )
    (net (code "82") (name "unconnected-(RP2-GPIO12-Pad32)") (class "Default")
      (node (ref "RP2") (pin "32") (pinfunction "GPIO12_32") (pintype "no_connect"))
    )
    (net (code "83") (name "unconnected-(RP2-GPIO13-Pad33)") (class "Default")
      (node (ref "RP2") (pin "33") (pinfunction "GPIO13_33") (pintype "no_connect"))
    )
    (net (code "84") (name "unconnected-(RP2-GPIO16-Pad36)") (class "Default")
      (node (ref "RP2") (pin "36") (pinfunction "GPIO16_36") (pintype "no_connect"))
    )
    (net (code "85") (name "unconnected-(RP2-GPIO17-Pad11)") (class "Default")
      (node (ref "RP2") (pin "11") (pinfunction "GPIO17_11") (pintype "bidirectional"))
    )
    (net (code "86") (name "unconnected-(RP2-GPIO18-Pad12)") (class "Default")
      (node (ref "RP2") (pin "12") (pinfunction "GPIO18_12") (pintype "bidirectional"))
    )
    (net (code "87") (name "unconnected-(RP2-GPIO19-Pad35)") (class "Default")
      (node (ref "RP2") (pin "35") (pinfunction "GPIO19_35") (pintype "no_connect"))
    )
    (net (code "88") (name "unconnected-(RP2-GPIO20-Pad38)") (class "Default")
      (node (ref "RP2") (pin "38") (pinfunction "GPIO20_38") (pintype "no_connect"))
    )
    (net (code "89") (name "unconnected-(RP2-GPIO21-Pad40)") (class "Default")
      (node (ref "RP2") (pin "40") (pinfunction "GPIO21_40") (pintype "no_connect"))
    )
    (net (code "90") (name "unconnected-(RP2-GPIO22-Pad15)") (class "Default")
      (node (ref "RP2") (pin "15") (pinfunction "GPIO22_15") (pintype "bidirectional"))
    )
    (net (code "91") (name "unconnected-(RP2-GPIO23-Pad16)") (class "Default")
      (node (ref "RP2") (pin "16") (pinfunction "GPIO23_16") (pintype "bidirectional"))
    )
    (net (code "92") (name "unconnected-(RP2-GPIO24-Pad18)") (class "Default")
      (node (ref "RP2") (pin "18") (pinfunction "GPIO24_18") (pintype "bidirectional"))
    )
    (net (code "93") (name "unconnected-(RP2-GPIO25-Pad22)") (class "Default")
      (node (ref "RP2") (pin "22") (pinfunction "GPIO25_22") (pintype "bidirectional"))
    )
    (net (code "94") (name "unconnected-(RP2-GPIO26-Pad37)") (class "Default")
      (node (ref "RP2") (pin "37") (pinfunction "GPIO26_37") (pintype "no_connect"))
    )
    (net (code "95") (name "unconnected-(RP2-GPIO27-Pad13)") (class "Default")
      (node (ref "RP2") (pin "13") (pinfunction "GPIO27_13") (pintype "bidirectional"))
    )
    (net (code "96") (name "unconnected-(RP2-ID_SC-Pad28)") (class "Default")
      (node (ref "RP2") (pin "28") (pinfunction "ID_SC_28") (pintype "no_connect"))
    )
    (net (code "97") (name "unconnected-(RP2-ID_SD-Pad27)") (class "Default")
      (node (ref "RP2") (pin "27") (pinfunction "ID_SD_27") (pintype "no_connect"))
    )
    (net (code "98") (name "unconnected-(RP2-SCL-Pad5)") (class "Default")
      (node (ref "RP2") (pin "5") (pinfunction "SCL_5") (pintype "bidirectional"))
    )
    (net (code "99") (name "unconnected-(RP2-SDA-Pad3)") (class "Default")
      (node (ref "RP2") (pin "3") (pinfunction "SDA_3") (pintype "bidirectional"))
    )
    (net (code "100") (name "unconnected-(RP2-SPI_CE0-Pad24)") (class "Default")
      (node (ref "RP2") (pin "24") (pinfunction "SPI_CE0_24") (pintype "bidirectional"))
    )
    (net (code "101") (name "unconnected-(RP2-SPI_MISO-Pad21)") (class "Default")
      (node (ref "RP2") (pin "21") (pinfunction "SPI_MISO_21") (pintype "bidirectional"))
    )
    (net (code "102") (name "unconnected-(RP2-SPI_MOSI-Pad19)") (class "Default")
      (node (ref "RP2") (pin "19") (pinfunction "SPI_MOSI_19") (pintype "bidirectional"))
    )
    (net (code "103") (name "unconnected-(RP2-SPI_SCLK-Pad23)") (class "Default")
      (node (ref "RP2") (pin "23") (pinfunction "SPI_SCLK_23") (pintype "bidirectional"))
    )
    (net (code "104") (name "unconnected-(RST_ARDU-Pad1)") (class "Default")
      (node (ref "RST_ARDU") (pin "1") (pinfunction "1_1") (pintype "passive"))
    )
    (net (code "105") (name "unconnected-(RST_ARDU-Pad3)") (class "Default")
      (node (ref "RST_ARDU") (pin "3") (pinfunction "3_3") (pintype "passive"))
    )
    (net (code "106") (name "unconnected-(RST_RP2-Pad2)") (class "Default")
      (node (ref "RST_RP2") (pin "2") (pinfunction "2_2") (pintype "passive"))
    )
    (net (code "107") (name "unconnected-(RST_RP2-Pad4)") (class "Default")
      (node (ref "RST_RP2") (pin "4") (pinfunction "4_4") (pintype "passive"))
    )
    (net (code "108") (name "unconnected-(SV11-Pad1)") (class "Default")
      (node (ref "SV11") (pin "1") (pinfunction "1_1") (pintype "passive"))
    )
    (net (code "109") (name "unconnected-(SV11-Pad2)") (class "Default")
      (node (ref "SV11") (pin "2") (pinfunction "2_2") (pintype "passive"))
    )
    (net (code "110") (name "unconnected-(SV11-Pad3)") (class "Default")
      (node (ref "SV11") (pin "3") (pinfunction "3_3") (pintype "passive"))
    )
    (net (code "111") (name "unconnected-(SV11-Pad4)") (class "Default")
      (node (ref "SV11") (pin "4") (pinfunction "4_4") (pintype "passive"))
    )
    (net (code "112") (name "unconnected-(SV11-Pad5)") (class "Default")
      (node (ref "SV11") (pin "5") (pinfunction "5_5") (pintype "passive"))
    )
    (net (code "113") (name "unconnected-(U$1-EXTCLK-Pad25)") (class "Default")
      (node (ref "U$1") (pin "25") (pinfunction "EXTCLK_25") (pintype "input"))
    )
    (net (code "114") (name "unconnected-(U$1-{slash}OE-Pad23)") (class "Default")
      (node (ref "U$1") (pin "23") (pinfunction "/OE_23") (pintype "bidirectional"))
    )
    (net (code "115") (name "unconnected-(U$2-ON{slash}OFF-Pad3)") (class "Default")
      (node (ref "U$2") (pin "3") (pinfunction "ON/OFF_3") (pintype "bidirectional"))
    )
    (net (code "116") (name "unconnected-(U1-*D5-PadD5)") (class "Default")
      (node (ref "U1") (pin "D5") (pinfunction "*D5_D5") (pintype "bidirectional"))
    )
    (net (code "117") (name "unconnected-(U1-Pad3.3V)") (class "Default")
      (node (ref "U1") (pin "3.3V") (pinfunction "3.3V_3.3V") (pintype "bidirectional"))
    )
    (net (code "118") (name "unconnected-(U1-PadA0)") (class "Default")
      (node (ref "U1") (pin "A0") (pinfunction "A0_A0") (pintype "bidirectional"))
    )
    (net (code "119") (name "unconnected-(U1-PadA1)") (class "Default")
      (node (ref "U1") (pin "A1") (pinfunction "A1_A1") (pintype "bidirectional"))
    )
    (net (code "120") (name "unconnected-(U1-PadA2)") (class "Default")
      (node (ref "U1") (pin "A2") (pinfunction "A2_A2") (pintype "bidirectional"))
    )
    (net (code "121") (name "unconnected-(U1-PadA3)") (class "Default")
      (node (ref "U1") (pin "A3") (pinfunction "A3_A3") (pintype "bidirectional"))
    )
    (net (code "122") (name "unconnected-(U1-PadAREF)") (class "Default")
      (node (ref "U1") (pin "AREF") (pinfunction "AREF_AREF") (pintype "bidirectional"))
    )
    (net (code "123") (name "unconnected-(U1-PadD12)") (class "Default")
      (node (ref "U1") (pin "D12") (pinfunction "D12_D12") (pintype "bidirectional"))
    )
    (net (code "124") (name "unconnected-(U1-PadIOREF)") (class "Default")
      (node (ref "U1") (pin "IOREF") (pinfunction "IOREF_IOREF") (pintype "bidirectional"))
    )
    (net (code "125") (name "unconnected-(U1-PadSCL)") (class "Default")
      (node (ref "U1") (pin "SCL") (pinfunction "SCL_SCL") (pintype "bidirectional"))
    )
    (net (code "126") (name "unconnected-(U1-PadSDA)") (class "Default")
      (node (ref "U1") (pin "SDA") (pinfunction "SDA_SDA") (pintype "bidirectional"))
    )
    (net (code "127") (name "unconnected-(U1-PadVIN)") (class "Default")
      (node (ref "U1") (pin "VIN") (pinfunction "VIN_VIN") (pintype "bidirectional"))
    )
  )
)
